# Shared_IoT_Dev.net
KiCad netlist of a schematic drawn in Altium Designer
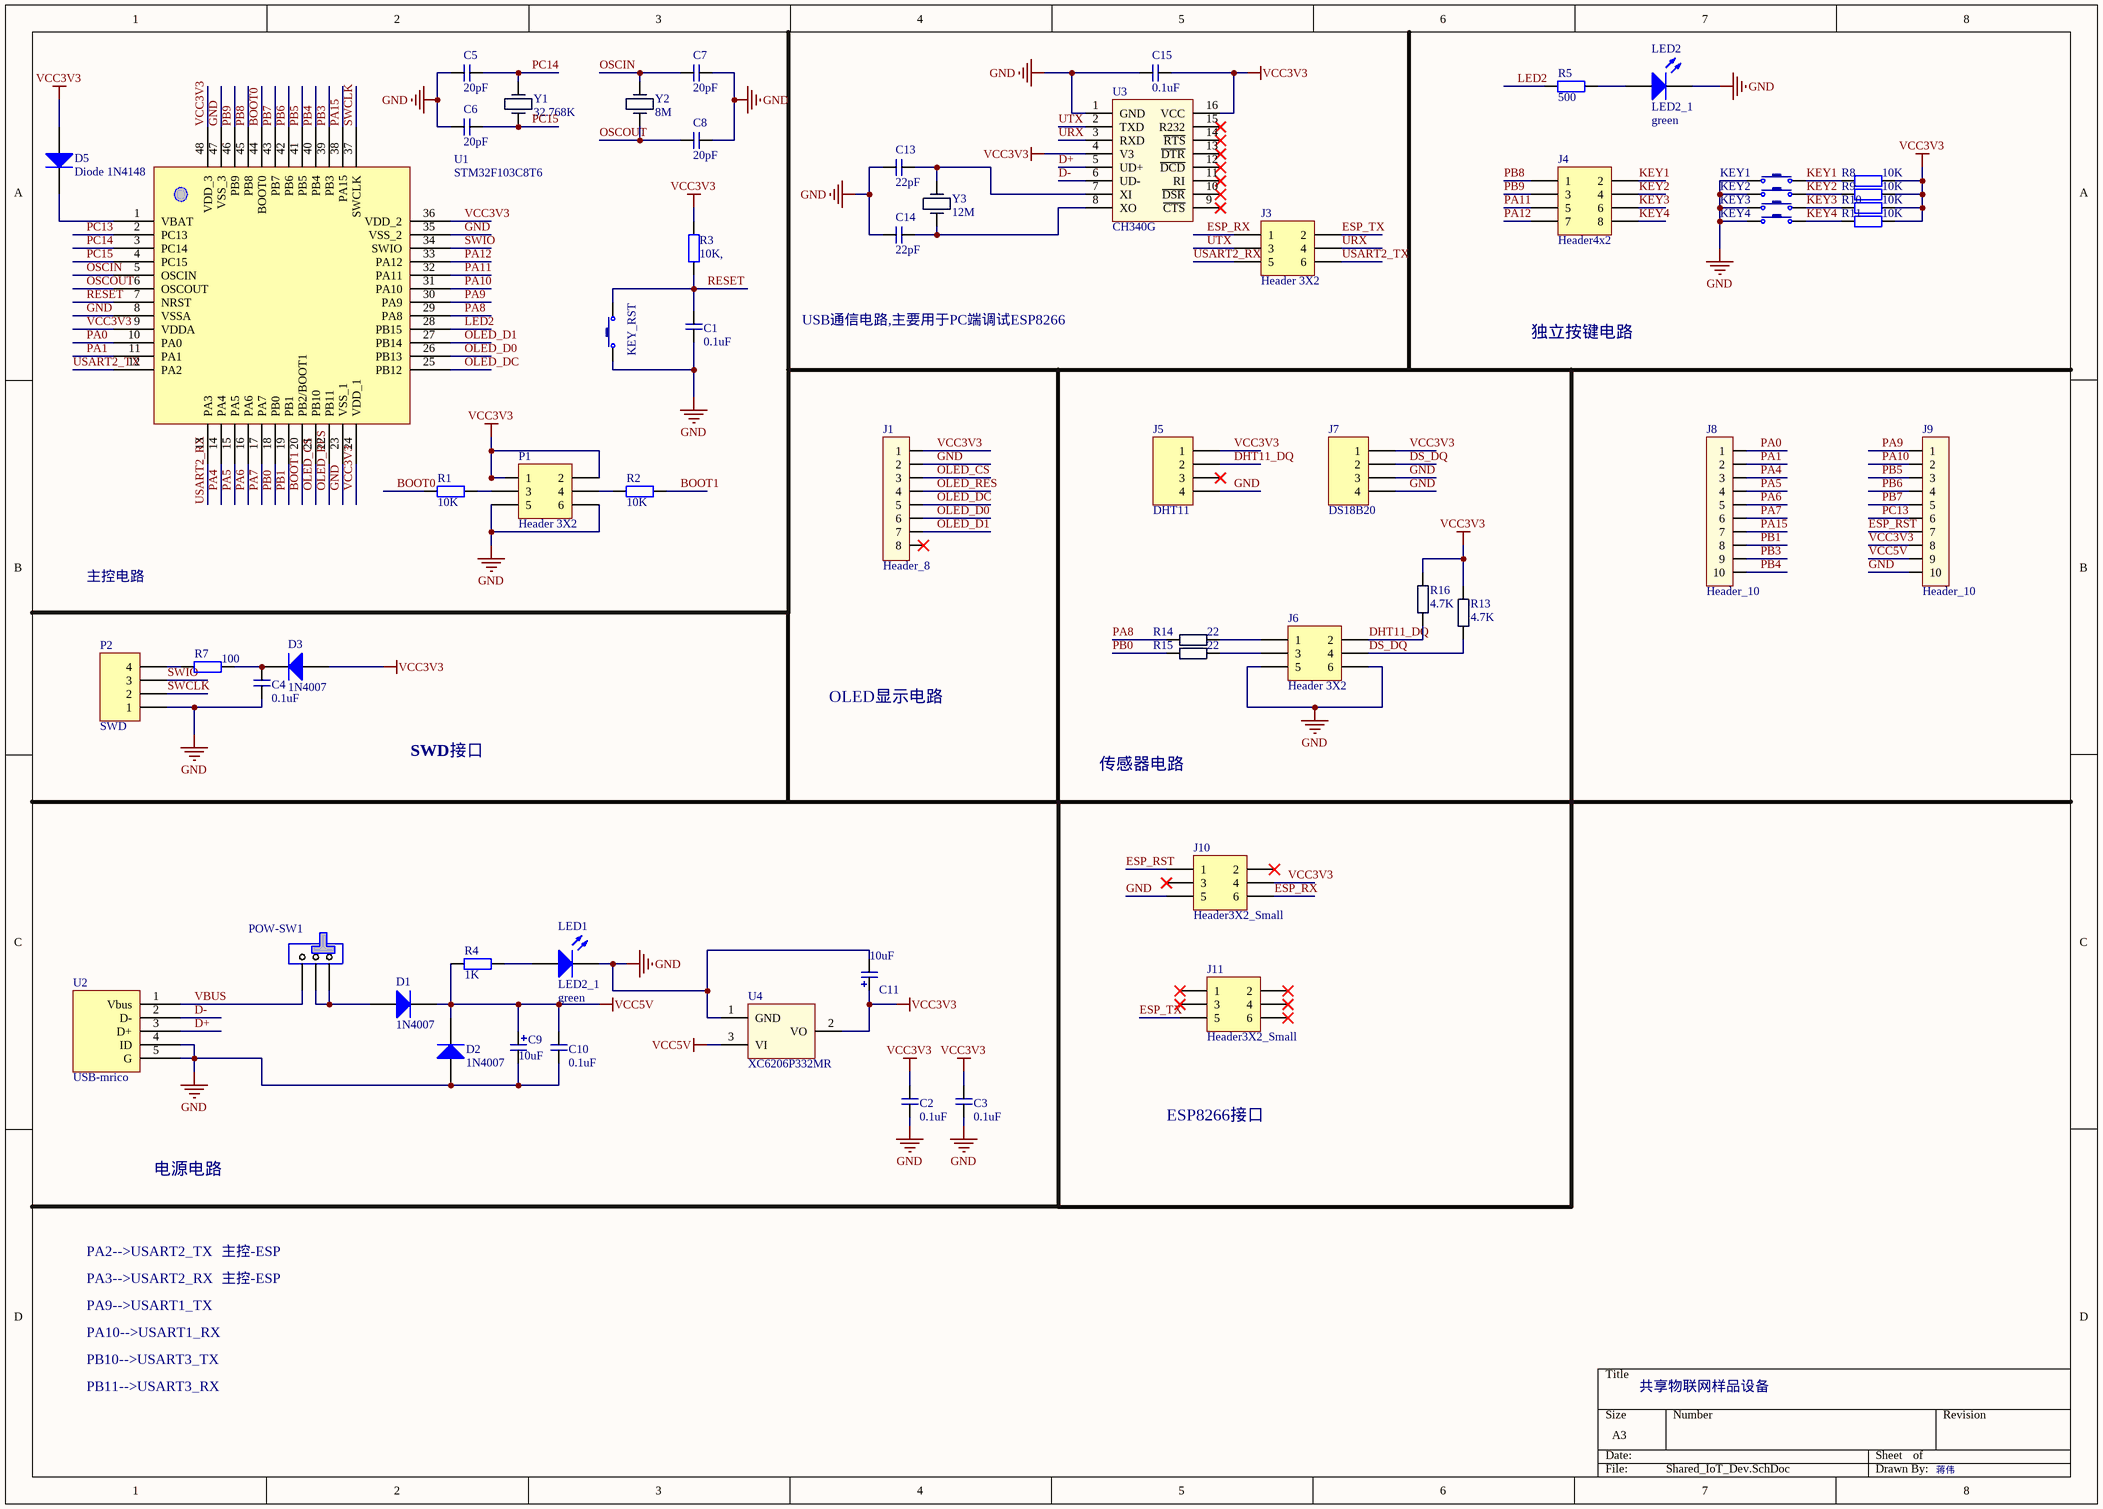
[diagram p0: Shared_IoT_Dev.SchDoc]

(export (version "E")
  (design (tool "Eeschema 10.0.6"))
  (components
    (comp (ref "C1")
      (value "0.1uF")
      (footprint "C0805")
      (description "CAP")
      (libsource (lib "Arduino") (part "CAP"))
    )
    (comp (ref "C2")
      (value "0.1uF")
      (footprint "C0805")
      (description "CAP")
      (libsource (lib "Arduino") (part "CAP"))
    )
    (comp (ref "C3")
      (value "0.1uF")
      (footprint "C0805")
      (description "CAP")
      (libsource (lib "Arduino") (part "CAP"))
    )
    (comp (ref "C4")
      (value "0.1uF")
      (footprint "C0805")
      (description "CAP")
      (libsource (lib "Arduino") (part "CAP"))
    )
    (comp (ref "C5")
      (value "20pF")
      (footprint "C0805")
      (description "CAP")
      (libsource (lib "Arduino") (part "CAP"))
    )
    (comp (ref "C6")
      (value "20pF")
      (footprint "C0805")
      (description "CAP")
      (libsource (lib "Arduino") (part "CAP"))
    )
    (comp (ref "C7")
      (value "20pF")
      (footprint "C0805")
      (description "CAP")
      (libsource (lib "Arduino") (part "CAP"))
    )
    (comp (ref "C8")
      (value "20pF")
      (footprint "C0805")
      (description "CAP")
      (libsource (lib "Arduino") (part "CAP"))
    )
    (comp (ref "C9")
      (value "10uF")
      (footprint "CAP-TH_POL")
      (description "CAP_POL")
      (libsource (lib "Arduino") (part "CAP_POL"))
    )
    (comp (ref "C10")
      (value "0.1uF")
      (footprint "C0805")
      (description "CAP")
      (libsource (lib "Arduino") (part "CAP"))
    )
    (comp (ref "C11")
      (value "10uF")
      (footprint "CAP-TH_POL")
      (description "CAP_POL")
      (libsource (lib "Arduino") (part "CAP_POL"))
    )
    (comp (ref "C13")
      (value "22pF")
      (footprint "C0805")
      (description "CAP")
      (libsource (lib "Arduino") (part "CAP"))
    )
    (comp (ref "C14")
      (value "22pF")
      (footprint "C0805")
      (description "CAP")
      (libsource (lib "Arduino") (part "CAP"))
    )
    (comp (ref "C15")
      (value "0.1uF")
      (footprint "C0805")
      (description "CAP")
      (libsource (lib "Arduino") (part "CAP"))
    )
    (comp (ref "D1") (value "1N4007") (footprint "SMA") (libsource (lib "电流测量仪仪主控板原理图7950") (part "DIODE")))
    (comp (ref "D2") (value "1N4007") (footprint "SMA") (libsource (lib "电流测量仪仪主控板原理图7950") (part "DIODE")))
    (comp (ref "D3") (value "1N4007") (footprint "SMA") (libsource (lib "电流测量仪仪主控板原理图7950") (part "DIODE")))
    (comp (ref "D5")
      (value "Diode 1N4148")
      (footprint "SMA")
      (description "High Conductance Fast Diode")
      (fields (field (name "PUBLISHER") "Altium Limited"))
      (libsource (lib "电流测量仪仪主控板原理图7950") (part "Diode 1N4148"))
    )
    (comp (ref "J1")
      (value "Header_8")
      (footprint "HDR-TH_8P-P2.54-V")
      (libsource (lib "Arduino") (part "Header_8"))
    )
    (comp (ref "J3")
      (value "Header 3X2")
      (footprint "HDR2X3")
      (description "Header, 3-Pin, Dual row")
      (fields (field (name "PUBLISHER") "Altium Limited"))
      (libsource (lib "STM32F103C8T6") (part "Header 3X2"))
    )
    (comp (ref "J4")
      (value "Header4x2")
      (footprint "HDR2X4")
      (libsource (lib "STM32F103C8T6") (part "Header4x2"))
    )
    (comp (ref "J5")
      (value "DHT11")
      (footprint "HDR1X4H")
      (description "Header, 4-Pin")
      (fields (field (name "PUBLISHER") "Altium Limited"))
      (libsource (lib "") (part "Header 4_1"))
    )
    (comp (ref "J6")
      (value "Header 3X2")
      (footprint "HDR2X3")
      (description "Header, 3-Pin, Dual row")
      (fields (field (name "PUBLISHER") "Altium Limited"))
      (libsource (lib "STM32F103C8T6") (part "Header 3X2"))
    )
    (comp (ref "J7")
      (value "DS18B20")
      (footprint "HDR1X4H")
      (description "Header, 4-Pin")
      (fields (field (name "PUBLISHER") "Altium Limited"))
      (libsource (lib "") (part "Header 4_1"))
    )
    (comp (ref "J8")
      (value "Header_10")
      (footprint "HDR-TH_10P-P2.54-V")
      (libsource (lib "") (part "Header_10_1"))
    )
    (comp (ref "J9")
      (value "Header_10")
      (footprint "HDR-TH_10P-P2.54-V")
      (libsource (lib "Arduino") (part "Header_10"))
    )
    (comp (ref "J10")
      (value "Header3X2_Small")
      (footprint "HDR3X2_Small")
      (libsource (lib "STM32F103C8T6") (part "Header3X2_Small"))
    )
    (comp (ref "J11")
      (value "Header3X2_Small")
      (footprint "HDR3X2_Small")
      (libsource (lib "STM32F103C8T6") (part "Header3X2_Small"))
    )
    (comp (ref "KEY1") (value "KEY") (footprint "KEY-TH_4P") (libsource (lib "Arduino") (part "KEY")))
    (comp (ref "KEY2") (value "KEY") (footprint "KEY-TH_4P") (libsource (lib "Arduino") (part "KEY")))
    (comp (ref "KEY3") (value "KEY") (footprint "KEY-TH_4P") (libsource (lib "Arduino") (part "KEY")))
    (comp (ref "KEY4") (value "KEY") (footprint "KEY-TH_4P") (libsource (lib "Arduino") (part "KEY")))
    (comp (ref "KEY_RST") (value "KEY") (footprint "KEY-TH_4P") (libsource (lib "Arduino") (part "KEY")))
    (comp (ref "LED1")
      (value "LED2_1")
      (footprint "0805C")
      (description "Typical RED, GREEN, YELLOW, AMBER GaAs LED")
      (fields (field (name "ALTIUM_UNNAMED_1") "green") (field (name "PUBLISHER") "Altium Limited"))
      (libsource (lib "电流测量仪仪主控板原理图7950") (part "LED2_1"))
    )
    (comp (ref "LED2")
      (value "LED2_1")
      (footprint "0805C")
      (description "Typical RED, GREEN, YELLOW, AMBER GaAs LED")
      (fields (field (name "ALTIUM_UNNAMED_1") "green") (field (name "PUBLISHER") "Altium Limited"))
      (libsource (lib "电流测量仪仪主控板原理图7950") (part "LED2_1"))
    )
    (comp (ref "P1")
      (value "Header 3X2")
      (footprint "HDR2X3")
      (description "Header, 3-Pin, Dual row")
      (fields (field (name "PUBLISHER") "Altium Limited"))
      (libsource (lib "STM32F103C8T6") (part "Header 3X2"))
    )
    (comp (ref "P2")
      (value "SWD")
      (footprint "HDR1X4H")
      (description "Header, 4-Pin")
      (fields (field (name "PUBLISHER") "Altium Limited"))
      (libsource (lib "STM32F103C8T6") (part "Header 4"))
    )
    (comp (ref "POW-SW1")
      (value "Switch")
      (footprint "SW")
      (libsource (lib "电流测量仪仪主控板原理图7950") (part "Swich_On_Off"))
    )
    (comp (ref "R1")
      (value "10K")
      (footprint "R0805")
      (description "Resistor")
      (fields (field (name "PUBLISHER") "Altium Limited"))
      (libsource (lib "STM32F103C8T6") (part "Res2"))
    )
    (comp (ref "R2")
      (value "10K")
      (footprint "R0805")
      (description "Resistor")
      (fields (field (name "PUBLISHER") "Altium Limited"))
      (libsource (lib "STM32F103C8T6") (part "Res2"))
    )
    (comp (ref "R3")
      (value "10K,")
      (footprint "R0805")
      (description "Resistor")
      (fields (field (name "PUBLISHER") "Altium Limited"))
      (libsource (lib "") (part "Res2_1"))
    )
    (comp (ref "R4")
      (value "1K")
      (footprint "0805R")
      (description "Resistor")
      (fields (field (name "Comment") "Res2") (field (name "PUBLISHER") "Altium Limited"))
      (libsource (lib "电流测量仪仪主控板原理图7950") (part "Res_3"))
    )
    (comp (ref "R5")
      (value "500")
      (footprint "0805R")
      (description "Resistor")
      (fields (field (name "Comment") "Res2") (field (name "PUBLISHER") "Altium Limited"))
      (libsource (lib "电流测量仪仪主控板原理图7950") (part "Res_3"))
    )
    (comp (ref "R7")
      (value "100")
      (footprint "0805R")
      (description "Resistor")
      (fields (field (name "PUBLISHER") "Altium Limited"))
      (libsource (lib "电流测量仪仪主控板原理图7950") (part "Res2"))
    )
    (comp (ref "R8")
      (value "10K")
      (footprint "0805R")
      (description "Resistor")
      (fields (field (name "Comment") "Res2") (field (name "PUBLISHER") "Altium Limited"))
      (libsource (lib "电流测量仪仪主控板原理图7950") (part "Res_3"))
    )
    (comp (ref "R9")
      (value "10K")
      (footprint "0805R")
      (description "Resistor")
      (fields (field (name "Comment") "Res2") (field (name "PUBLISHER") "Altium Limited"))
      (libsource (lib "电流测量仪仪主控板原理图7950") (part "Res_3"))
    )
    (comp (ref "R10")
      (value "10K")
      (footprint "0805R")
      (description "Resistor")
      (fields (field (name "Comment") "Res2") (field (name "PUBLISHER") "Altium Limited"))
      (libsource (lib "电流测量仪仪主控板原理图7950") (part "Res_3"))
    )
    (comp (ref "R11")
      (value "10K")
      (footprint "0805R")
      (description "Resistor")
      (fields (field (name "Comment") "Res2") (field (name "PUBLISHER") "Altium Limited"))
      (libsource (lib "电流测量仪仪主控板原理图7950") (part "Res_3"))
    )
    (comp (ref "R13")
      (value "4.7K")
      (footprint "R0805")
      (description "RES")
      (libsource (lib "Arduino") (part "RES"))
    )
    (comp (ref "R14")
      (value "22")
      (footprint "R0805")
      (description "RES")
      (libsource (lib "Arduino") (part "RES"))
    )
    (comp (ref "R15")
      (value "22")
      (footprint "R0805")
      (description "RES")
      (libsource (lib "Arduino") (part "RES"))
    )
    (comp (ref "R16")
      (value "4.7K")
      (footprint "R0805")
      (description "RES")
      (libsource (lib "Arduino") (part "RES"))
    )
    (comp (ref "U1")
      (value "STM32F103C8T6")
      (footprint "48P")
      (libsource (lib "STM32F103C8T6") (part "STM32F103C8T6"))
    )
    (comp (ref "U2")
      (value "USB-mrico")
      (footprint "Micro_USB")
      (libsource (lib "STM32F103C8T6") (part "usb-STM"))
    )
    (comp (ref "U3") (value "CH340G") (footprint "CH340G_SOIC") (libsource (lib "Arduino") (part "CH340G")))
    (comp (ref "U4")
      (value "XC6206P332MR")
      (footprint "XC_SOT-23-3")
      (description "XC6206P332MR Power Lower to 3.3v")
      (libsource (lib "Arduino") (part "XC6206P332MR"))
    )
    (comp (ref "Y1")
      (value "32.768K")
      (footprint "CRYSTAL")
      (description "CRYSTAL")
      (libsource (lib "Arduino") (part "CRYSTAL"))
    )
    (comp (ref "Y2")
      (value "8M")
      (footprint "CRYSTAL")
      (description "CRYSTAL")
      (libsource (lib "Arduino") (part "CRYSTAL"))
    )
    (comp (ref "Y3")
      (value "12M")
      (footprint "CRYSTAL")
      (description "CRYSTAL")
      (libsource (lib "Arduino") (part "CRYSTAL"))
    )
  )
  (nets
    (net (code "1") (name "/BOOT0") (class "Default")
      (node (ref "R1") (pin "1") (pinfunction "1_1") (pintype "passive"))
      (node (ref "U1") (pin "44") (pinfunction "BOOT0_44") (pintype "passive"))
    )
    (net (code "2") (name "/BOOT1") (class "Default")
      (node (ref "R2") (pin "2") (pinfunction "2_2") (pintype "passive"))
      (node (ref "U1") (pin "20") (pinfunction "PB2/BOOT1_20") (pintype "passive"))
    )
    (net (code "3") (name "/D+") (class "Default")
      (node (ref "U2") (pin "3") (pinfunction "D+_3") (pintype "passive"))
      (node (ref "U3") (pin "5") (pinfunction "UD+_5") (pintype "passive"))
    )
    (net (code "4") (name "/D-") (class "Default")
      (node (ref "U2") (pin "2") (pinfunction "D-_2") (pintype "passive"))
      (node (ref "U3") (pin "6") (pinfunction "UD-_6") (pintype "passive"))
    )
    (net (code "5") (name "/DHT11_DQ") (class "Default")
      (node (ref "J5") (pin "2") (pinfunction "2_2") (pintype "passive"))
      (node (ref "J6") (pin "2") (pinfunction "2_2") (pintype "passive"))
      (node (ref "R16") (pin "1") (pinfunction "1_1") (pintype "passive"))
    )
    (net (code "6") (name "/DS_DQ") (class "Default")
      (node (ref "J6") (pin "4") (pinfunction "4_4") (pintype "passive"))
      (node (ref "J7") (pin "2") (pinfunction "2_2") (pintype "passive"))
      (node (ref "R13") (pin "1") (pinfunction "1_1") (pintype "passive"))
    )
    (net (code "7") (name "/ESP_RST") (class "Default")
      (node (ref "J10") (pin "1") (pinfunction "1_1") (pintype "passive"))
      (node (ref "J9") (pin "7") (pinfunction "7_7") (pintype "passive"))
    )
    (net (code "8") (name "/ESP_RX") (class "Default")
      (node (ref "J10") (pin "6") (pinfunction "6_6") (pintype "passive"))
      (node (ref "J3") (pin "1") (pinfunction "1_1") (pintype "passive"))
    )
    (net (code "9") (name "/ESP_TX") (class "Default")
      (node (ref "J11") (pin "5") (pinfunction "5_5") (pintype "passive"))
      (node (ref "J3") (pin "2") (pinfunction "2_2") (pintype "passive"))
    )
    (net (code "10") (name "/KEY1") (class "Default")
      (node (ref "J4") (pin "2") (pinfunction "2_2") (pintype "passive"))
      (node (ref "KEY1") (pin "3") (pinfunction "3_3") (pintype "passive"))
      (node (ref "R8") (pin "1") (pinfunction "1_1") (pintype "passive"))
    )
    (net (code "11") (name "/KEY2") (class "Default")
      (node (ref "J4") (pin "4") (pinfunction "4_4") (pintype "passive"))
      (node (ref "KEY2") (pin "3") (pinfunction "3_3") (pintype "passive"))
      (node (ref "R9") (pin "1") (pinfunction "1_1") (pintype "passive"))
    )
    (net (code "12") (name "/KEY3") (class "Default")
      (node (ref "J4") (pin "6") (pinfunction "6_6") (pintype "passive"))
      (node (ref "KEY3") (pin "3") (pinfunction "3_3") (pintype "passive"))
      (node (ref "R10") (pin "1") (pinfunction "1_1") (pintype "passive"))
    )
    (net (code "13") (name "/KEY4") (class "Default")
      (node (ref "J4") (pin "8") (pinfunction "8_8") (pintype "passive"))
      (node (ref "KEY4") (pin "3") (pinfunction "3_3") (pintype "passive"))
      (node (ref "R11") (pin "1") (pinfunction "1_1") (pintype "passive"))
    )
    (net (code "14") (name "/LED2") (class "Default")
      (node (ref "R5") (pin "1") (pinfunction "1_1") (pintype "passive"))
      (node (ref "U1") (pin "28") (pinfunction "PB15_28") (pintype "passive"))
    )
    (net (code "15") (name "/OLED_CS") (class "Default")
      (node (ref "J1") (pin "3") (pinfunction "3_3") (pintype "passive"))
      (node (ref "U1") (pin "21") (pinfunction "PB10_21") (pintype "passive"))
    )
    (net (code "16") (name "/OLED_D0") (class "Default")
      (node (ref "J1") (pin "6") (pinfunction "6_6") (pintype "passive"))
      (node (ref "U1") (pin "26") (pinfunction "PB13_26") (pintype "passive"))
    )
    (net (code "17") (name "/OLED_D1") (class "Default")
      (node (ref "J1") (pin "7") (pinfunction "7_7") (pintype "passive"))
      (node (ref "U1") (pin "27") (pinfunction "PB14_27") (pintype "passive"))
    )
    (net (code "18") (name "/OLED_DC") (class "Default")
      (node (ref "J1") (pin "5") (pinfunction "5_5") (pintype "passive"))
      (node (ref "U1") (pin "25") (pinfunction "PB12_25") (pintype "passive"))
    )
    (net (code "19") (name "/OLED_RES") (class "Default")
      (node (ref "J1") (pin "4") (pinfunction "4_4") (pintype "passive"))
      (node (ref "U1") (pin "22") (pinfunction "PB11_22") (pintype "passive"))
    )
    (net (code "20") (name "/OSCIN") (class "Default")
      (node (ref "C7") (pin "1") (pinfunction "1_1") (pintype "passive"))
      (node (ref "U1") (pin "5") (pinfunction "OSCIN_5") (pintype "passive"))
      (node (ref "Y2") (pin "2") (pinfunction "2_2") (pintype "passive"))
    )
    (net (code "21") (name "/OSCOUT") (class "Default")
      (node (ref "C8") (pin "1") (pinfunction "1_1") (pintype "passive"))
      (node (ref "U1") (pin "6") (pinfunction "OSCOUT_6") (pintype "passive"))
      (node (ref "Y2") (pin "1") (pinfunction "1_1") (pintype "passive"))
    )
    (net (code "22") (name "/PA0") (class "Default")
      (node (ref "J8") (pin "1") (pinfunction "1_1") (pintype "passive"))
      (node (ref "U1") (pin "10") (pinfunction "PA0_10") (pintype "passive"))
    )
    (net (code "23") (name "/PA1") (class "Default")
      (node (ref "J8") (pin "2") (pinfunction "2_2") (pintype "passive"))
      (node (ref "U1") (pin "11") (pinfunction "PA1_11") (pintype "passive"))
    )
    (net (code "24") (name "/PA4") (class "Default")
      (node (ref "J8") (pin "3") (pinfunction "3_3") (pintype "passive"))
      (node (ref "U1") (pin "14") (pinfunction "PA4_14") (pintype "passive"))
    )
    (net (code "25") (name "/PA5") (class "Default")
      (node (ref "J8") (pin "4") (pinfunction "4_4") (pintype "passive"))
      (node (ref "U1") (pin "15") (pinfunction "PA5_15") (pintype "passive"))
    )
    (net (code "26") (name "/PA6") (class "Default")
      (node (ref "J8") (pin "5") (pinfunction "5_5") (pintype "passive"))
      (node (ref "U1") (pin "16") (pinfunction "PA6_16") (pintype "passive"))
    )
    (net (code "27") (name "/PA7") (class "Default")
      (node (ref "J8") (pin "6") (pinfunction "6_6") (pintype "passive"))
      (node (ref "U1") (pin "17") (pinfunction "PA7_17") (pintype "passive"))
    )
    (net (code "28") (name "/PA8") (class "Default")
      (node (ref "R14") (pin "2") (pinfunction "2_2") (pintype "passive"))
      (node (ref "U1") (pin "29") (pinfunction "PA8_29") (pintype "passive"))
    )
    (net (code "29") (name "/PA9") (class "Default")
      (node (ref "J9") (pin "1") (pinfunction "1_1") (pintype "passive"))
      (node (ref "U1") (pin "30") (pinfunction "PA9_30") (pintype "passive"))
    )
    (net (code "30") (name "/PA10") (class "Default")
      (node (ref "J9") (pin "2") (pinfunction "2_2") (pintype "passive"))
      (node (ref "U1") (pin "31") (pinfunction "PA10_31") (pintype "passive"))
    )
    (net (code "31") (name "/PA11") (class "Default")
      (node (ref "J4") (pin "5") (pinfunction "5_5") (pintype "passive"))
      (node (ref "U1") (pin "32") (pinfunction "PA11_32") (pintype "passive"))
    )
    (net (code "32") (name "/PA12") (class "Default")
      (node (ref "J4") (pin "7") (pinfunction "7_7") (pintype "passive"))
      (node (ref "U1") (pin "33") (pinfunction "PA12_33") (pintype "passive"))
    )
    (net (code "33") (name "/PA15") (class "Default")
      (node (ref "J8") (pin "7") (pinfunction "7_7") (pintype "passive"))
      (node (ref "U1") (pin "38") (pinfunction "PA15_38") (pintype "passive"))
    )
    (net (code "34") (name "/PB0") (class "Default")
      (node (ref "R15") (pin "2") (pinfunction "2_2") (pintype "passive"))
      (node (ref "U1") (pin "18") (pinfunction "PB0_18") (pintype "passive"))
    )
    (net (code "35") (name "/PB1") (class "Default")
      (node (ref "J8") (pin "8") (pinfunction "8_8") (pintype "passive"))
      (node (ref "U1") (pin "19") (pinfunction "PB1_19") (pintype "passive"))
    )
    (net (code "36") (name "/PB3") (class "Default")
      (node (ref "J8") (pin "9") (pinfunction "9_9") (pintype "passive"))
      (node (ref "U1") (pin "39") (pinfunction "PB3_39") (pintype "passive"))
    )
    (net (code "37") (name "/PB4") (class "Default")
      (node (ref "J8") (pin "10") (pinfunction "10_10") (pintype "passive"))
      (node (ref "U1") (pin "40") (pinfunction "PB4_40") (pintype "passive"))
    )
    (net (code "38") (name "/PB5") (class "Default")
      (node (ref "J9") (pin "3") (pinfunction "3_3") (pintype "passive"))
      (node (ref "U1") (pin "41") (pinfunction "PB5_41") (pintype "passive"))
    )
    (net (code "39") (name "/PB6") (class "Default")
      (node (ref "J9") (pin "4") (pinfunction "4_4") (pintype "passive"))
      (node (ref "U1") (pin "42") (pinfunction "PB6_42") (pintype "passive"))
    )
    (net (code "40") (name "/PB7") (class "Default")
      (node (ref "J9") (pin "5") (pinfunction "5_5") (pintype "passive"))
      (node (ref "U1") (pin "43") (pinfunction "PB7_43") (pintype "passive"))
    )
    (net (code "41") (name "/PB8") (class "Default")
      (node (ref "J4") (pin "1") (pinfunction "1_1") (pintype "passive"))
      (node (ref "U1") (pin "45") (pinfunction "PB8_45") (pintype "passive"))
    )
    (net (code "42") (name "/PB9") (class "Default")
      (node (ref "J4") (pin "3") (pinfunction "3_3") (pintype "passive"))
      (node (ref "U1") (pin "46") (pinfunction "PB9_46") (pintype "passive"))
    )
    (net (code "43") (name "/PC13") (class "Default")
      (node (ref "J9") (pin "6") (pinfunction "6_6") (pintype "passive"))
      (node (ref "U1") (pin "2") (pinfunction "PC13_2") (pintype "passive"))
    )
    (net (code "44") (name "/PC14") (class "Default")
      (node (ref "C5") (pin "2") (pinfunction "2_2") (pintype "passive"))
      (node (ref "U1") (pin "3") (pinfunction "PC14_3") (pintype "passive"))
      (node (ref "Y1") (pin "2") (pinfunction "2_2") (pintype "passive"))
    )
    (net (code "45") (name "/PC15") (class "Default")
      (node (ref "C6") (pin "2") (pinfunction "2_2") (pintype "passive"))
      (node (ref "U1") (pin "4") (pinfunction "PC15_4") (pintype "passive"))
      (node (ref "Y1") (pin "1") (pinfunction "1_1") (pintype "passive"))
    )
    (net (code "46") (name "/RESET") (class "Default")
      (node (ref "C1") (pin "1") (pinfunction "1_1") (pintype "passive"))
      (node (ref "KEY_RST") (pin "3") (pinfunction "3_3") (pintype "passive"))
      (node (ref "R3") (pin "1") (pinfunction "1_1") (pintype "passive"))
      (node (ref "U1") (pin "7") (pinfunction "NRST_7") (pintype "passive"))
    )
    (net (code "47") (name "/SWCLK") (class "Default")
      (node (ref "P2") (pin "2") (pinfunction "2_2") (pintype "passive"))
      (node (ref "U1") (pin "37") (pinfunction "SWCLK_37") (pintype "passive"))
    )
    (net (code "48") (name "/SWIO") (class "Default")
      (node (ref "P2") (pin "3") (pinfunction "3_3") (pintype "passive"))
      (node (ref "U1") (pin "34") (pinfunction "SWIO_34") (pintype "passive"))
    )
    (net (code "49") (name "/URX") (class "Default")
      (node (ref "J3") (pin "4") (pinfunction "4_4") (pintype "passive"))
      (node (ref "U3") (pin "3") (pinfunction "RXD_3") (pintype "passive"))
    )
    (net (code "50") (name "/USART2_RX") (class "Default")
      (node (ref "J3") (pin "5") (pinfunction "5_5") (pintype "passive"))
      (node (ref "U1") (pin "13") (pinfunction "PA3_13") (pintype "passive"))
    )
    (net (code "51") (name "/USART2_TX") (class "Default")
      (node (ref "J3") (pin "6") (pinfunction "6_6") (pintype "passive"))
      (node (ref "U1") (pin "12") (pinfunction "PA2_12") (pintype "passive"))
    )
    (net (code "52") (name "/UTX") (class "Default")
      (node (ref "J3") (pin "3") (pinfunction "3_3") (pintype "passive"))
      (node (ref "U3") (pin "2") (pinfunction "TXD_2") (pintype "passive"))
    )
    (net (code "53") (name "/VBUS") (class "Default")
      (node (ref "POW-SW1") (pin "1") (pinfunction "1_1") (pintype "passive"))
      (node (ref "U2") (pin "1") (pinfunction "Vbus_1") (pintype "passive"))
    )
    (net (code "54") (name "GND") (class "Default")
      (node (ref "C1") (pin "2") (pinfunction "2_2") (pintype "passive"))
      (node (ref "C10") (pin "1") (pinfunction "1_1") (pintype "passive"))
      (node (ref "C11") (pin "2") (pinfunction "2_2") (pintype "passive"))
      (node (ref "C13") (pin "2") (pinfunction "2_2") (pintype "passive"))
      (node (ref "C14") (pin "2") (pinfunction "2_2") (pintype "passive"))
      (node (ref "C15") (pin "2") (pinfunction "2_2") (pintype "passive"))
      (node (ref "C2") (pin "2") (pinfunction "2_2") (pintype "passive"))
      (node (ref "C3") (pin "2") (pinfunction "2_2") (pintype "passive"))
      (node (ref "C4") (pin "2") (pinfunction "2_2") (pintype "passive"))
      (node (ref "C5") (pin "1") (pinfunction "1_1") (pintype "passive"))
      (node (ref "C6") (pin "1") (pinfunction "1_1") (pintype "passive"))
      (node (ref "C7") (pin "2") (pinfunction "2_2") (pintype "passive"))
      (node (ref "C8") (pin "2") (pinfunction "2_2") (pintype "passive"))
      (node (ref "C9") (pin "2") (pinfunction "2_2") (pintype "passive"))
      (node (ref "D2") (pin "1") (pinfunction "A_1") (pintype "passive"))
      (node (ref "J1") (pin "2") (pinfunction "2_2") (pintype "passive"))
      (node (ref "J10") (pin "5") (pinfunction "5_5") (pintype "passive"))
      (node (ref "J5") (pin "4") (pinfunction "4_4") (pintype "passive"))
      (node (ref "J6") (pin "5") (pinfunction "5_5") (pintype "passive"))
      (node (ref "J6") (pin "6") (pinfunction "6_6") (pintype "passive"))
      (node (ref "J7") (pin "3") (pinfunction "3_3") (pintype "passive"))
      (node (ref "J7") (pin "4") (pinfunction "4_4") (pintype "passive"))
      (node (ref "J9") (pin "10") (pinfunction "10_10") (pintype "passive"))
      (node (ref "KEY1") (pin "1") (pinfunction "1_1") (pintype "passive"))
      (node (ref "KEY2") (pin "1") (pinfunction "1_1") (pintype "passive"))
      (node (ref "KEY3") (pin "1") (pinfunction "1_1") (pintype "passive"))
      (node (ref "KEY4") (pin "1") (pinfunction "1_1") (pintype "passive"))
      (node (ref "KEY_RST") (pin "1") (pinfunction "1_1") (pintype "passive"))
      (node (ref "LED1") (pin "2") (pinfunction "K_2") (pintype "passive"))
      (node (ref "LED2") (pin "2") (pinfunction "K_2") (pintype "passive"))
      (node (ref "P1") (pin "5") (pinfunction "5_5") (pintype "passive"))
      (node (ref "P1") (pin "6") (pinfunction "6_6") (pintype "passive"))
      (node (ref "P2") (pin "1") (pinfunction "1_1") (pintype "passive"))
      (node (ref "U1") (pin "23") (pinfunction "VSS_1_23") (pintype "passive"))
      (node (ref "U1") (pin "35") (pinfunction "VSS_2_35") (pintype "passive"))
      (node (ref "U1") (pin "47") (pinfunction "VSS_3_47") (pintype "passive"))
      (node (ref "U1") (pin "8") (pinfunction "VSSA_8") (pintype "passive"))
      (node (ref "U2") (pin "4") (pinfunction "ID_4") (pintype "passive"))
      (node (ref "U2") (pin "5") (pinfunction "G_5") (pintype "passive"))
      (node (ref "U3") (pin "1") (pinfunction "GND_1") (pintype "passive"))
      (node (ref "U4") (pin "1") (pinfunction "GND_1") (pintype "passive"))
    )
    (net (code "55") (name "Net-(D1-A)") (class "Default")
      (node (ref "D1") (pin "1") (pinfunction "A_1") (pintype "passive"))
      (node (ref "POW-SW1") (pin "2") (pinfunction "2_2") (pintype "passive"))
      (node (ref "POW-SW1") (pin "3") (pinfunction "3_3") (pintype "passive"))
    )
    (net (code "56") (name "Net-(D3-K)") (class "Default")
      (node (ref "C4") (pin "1") (pinfunction "1_1") (pintype "passive"))
      (node (ref "D3") (pin "2") (pinfunction "K_2") (pintype "passive"))
      (node (ref "R7") (pin "2") (pinfunction "2_2") (pintype "passive"))
    )
    (net (code "57") (name "Net-(D5-K)") (class "Default")
      (node (ref "D5") (pin "2") (pinfunction "K_2") (pintype "passive"))
      (node (ref "U1") (pin "1") (pinfunction "VBAT_1") (pintype "passive"))
    )
    (net (code "58") (name "Net-(J6-Pad1)") (class "Default")
      (node (ref "J6") (pin "1") (pinfunction "1_1") (pintype "passive"))
      (node (ref "R14") (pin "1") (pinfunction "1_1") (pintype "passive"))
    )
    (net (code "59") (name "Net-(J6-Pad3)") (class "Default")
      (node (ref "J6") (pin "3") (pinfunction "3_3") (pintype "passive"))
      (node (ref "R15") (pin "1") (pinfunction "1_1") (pintype "passive"))
    )
    (net (code "60") (name "Net-(LED1-A)") (class "Default")
      (node (ref "LED1") (pin "1") (pinfunction "A_1") (pintype "passive"))
      (node (ref "R4") (pin "2") (pinfunction "2_2") (pintype "passive"))
    )
    (net (code "61") (name "Net-(LED2-A)") (class "Default")
      (node (ref "LED2") (pin "1") (pinfunction "A_1") (pintype "passive"))
      (node (ref "R5") (pin "2") (pinfunction "2_2") (pintype "passive"))
    )
    (net (code "62") (name "Net-(P1-Pad3)") (class "Default")
      (node (ref "P1") (pin "3") (pinfunction "3_3") (pintype "passive"))
      (node (ref "R1") (pin "2") (pinfunction "2_2") (pintype "passive"))
    )
    (net (code "63") (name "Net-(P1-Pad4)") (class "Default")
      (node (ref "P1") (pin "4") (pinfunction "4_4") (pintype "passive"))
      (node (ref "R2") (pin "1") (pinfunction "1_1") (pintype "passive"))
    )
    (net (code "64") (name "Net-(P2-Pad4)") (class "Default")
      (node (ref "P2") (pin "4") (pinfunction "4_4") (pintype "passive"))
      (node (ref "R7") (pin "1") (pinfunction "1_1") (pintype "passive"))
    )
    (net (code "65") (name "Net-(U3-XI)") (class "Default")
      (node (ref "C13") (pin "1") (pinfunction "1_1") (pintype "passive"))
      (node (ref "U3") (pin "7") (pinfunction "XI_7") (pintype "passive"))
      (node (ref "Y3") (pin "2") (pinfunction "2_2") (pintype "passive"))
    )
    (net (code "66") (name "Net-(U3-XO)") (class "Default")
      (node (ref "C14") (pin "1") (pinfunction "1_1") (pintype "passive"))
      (node (ref "U3") (pin "8") (pinfunction "XO_8") (pintype "passive"))
      (node (ref "Y3") (pin "1") (pinfunction "1_1") (pintype "passive"))
    )
    (net (code "67") (name "VCC3V3") (class "Default")
      (node (ref "C11") (pin "1") (pinfunction "1_1") (pintype "passive"))
      (node (ref "C15") (pin "1") (pinfunction "1_1") (pintype "passive"))
      (node (ref "C2") (pin "1") (pinfunction "1_1") (pintype "passive"))
      (node (ref "C3") (pin "1") (pinfunction "1_1") (pintype "passive"))
      (node (ref "D3") (pin "1") (pinfunction "A_1") (pintype "passive"))
      (node (ref "D5") (pin "1") (pinfunction "A_1") (pintype "passive"))
      (node (ref "J1") (pin "1") (pinfunction "1_1") (pintype "passive"))
      (node (ref "J10") (pin "4") (pinfunction "4_4") (pintype "passive"))
      (node (ref "J5") (pin "1") (pinfunction "1_1") (pintype "passive"))
      (node (ref "J7") (pin "1") (pinfunction "1_1") (pintype "passive"))
      (node (ref "J9") (pin "8") (pinfunction "8_8") (pintype "passive"))
      (node (ref "P1") (pin "1") (pinfunction "1_1") (pintype "passive"))
      (node (ref "P1") (pin "2") (pinfunction "2_2") (pintype "passive"))
      (node (ref "R10") (pin "2") (pinfunction "2_2") (pintype "passive"))
      (node (ref "R11") (pin "2") (pinfunction "2_2") (pintype "passive"))
      (node (ref "R13") (pin "2") (pinfunction "2_2") (pintype "passive"))
      (node (ref "R16") (pin "2") (pinfunction "2_2") (pintype "passive"))
      (node (ref "R3") (pin "2") (pinfunction "2_2") (pintype "passive"))
      (node (ref "R8") (pin "2") (pinfunction "2_2") (pintype "passive"))
      (node (ref "R9") (pin "2") (pinfunction "2_2") (pintype "passive"))
      (node (ref "U1") (pin "24") (pinfunction "VDD_1_24") (pintype "passive"))
      (node (ref "U1") (pin "36") (pinfunction "VDD_2_36") (pintype "passive"))
      (node (ref "U1") (pin "48") (pinfunction "VDD_3_48") (pintype "passive"))
      (node (ref "U1") (pin "9") (pinfunction "VDDA_9") (pintype "passive"))
      (node (ref "U3") (pin "16") (pinfunction "VCC_16") (pintype "passive"))
      (node (ref "U3") (pin "4") (pinfunction "V3_4") (pintype "passive"))
      (node (ref "U4") (pin "2") (pinfunction "VO_2") (pintype "passive"))
    )
    (net (code "68") (name "VCC5V") (class "Default")
      (node (ref "C10") (pin "2") (pinfunction "2_2") (pintype "passive"))
      (node (ref "C9") (pin "1") (pinfunction "1_1") (pintype "passive"))
      (node (ref "D1") (pin "2") (pinfunction "K_2") (pintype "passive"))
      (node (ref "D2") (pin "2") (pinfunction "K_2") (pintype "passive"))
      (node (ref "J9") (pin "9") (pinfunction "9_9") (pintype "passive"))
      (node (ref "R4") (pin "1") (pinfunction "1_1") (pintype "passive"))
      (node (ref "U4") (pin "3") (pinfunction "VI_3") (pintype "passive"))
    )
    (net (code "69") (name "unconnected-(J1-Pad8)") (class "Default")
      (node (ref "J1") (pin "8") (pinfunction "8_8") (pintype "passive+no_connect"))
    )
    (net (code "70") (name "unconnected-(J5-Pad3)") (class "Default")
      (node (ref "J5") (pin "3") (pinfunction "3_3") (pintype "passive+no_connect"))
    )
    (net (code "71") (name "unconnected-(J10-Pad2)") (class "Default")
      (node (ref "J10") (pin "2") (pinfunction "2_2") (pintype "passive+no_connect"))
    )
    (net (code "72") (name "unconnected-(J10-Pad3)") (class "Default")
      (node (ref "J10") (pin "3") (pinfunction "3_3") (pintype "passive+no_connect"))
    )
    (net (code "73") (name "unconnected-(J11-Pad1)") (class "Default")
      (node (ref "J11") (pin "1") (pinfunction "1_1") (pintype "passive+no_connect"))
    )
    (net (code "74") (name "unconnected-(J11-Pad2)") (class "Default")
      (node (ref "J11") (pin "2") (pinfunction "2_2") (pintype "passive+no_connect"))
    )
    (net (code "75") (name "unconnected-(J11-Pad3)") (class "Default")
      (node (ref "J11") (pin "3") (pinfunction "3_3") (pintype "passive+no_connect"))
    )
    (net (code "76") (name "unconnected-(J11-Pad4)") (class "Default")
      (node (ref "J11") (pin "4") (pinfunction "4_4") (pintype "passive+no_connect"))
    )
    (net (code "77") (name "unconnected-(J11-Pad6)") (class "Default")
      (node (ref "J11") (pin "6") (pinfunction "6_6") (pintype "passive+no_connect"))
    )
    (net (code "78") (name "unconnected-(KEY1-Pad2)") (class "Default")
      (node (ref "KEY1") (pin "2") (pinfunction "2_2") (pintype "passive"))
    )
    (net (code "79") (name "unconnected-(KEY1-Pad4)") (class "Default")
      (node (ref "KEY1") (pin "4") (pinfunction "4_4") (pintype "passive"))
    )
    (net (code "80") (name "unconnected-(KEY2-Pad2)") (class "Default")
      (node (ref "KEY2") (pin "2") (pinfunction "2_2") (pintype "passive"))
    )
    (net (code "81") (name "unconnected-(KEY2-Pad4)") (class "Default")
      (node (ref "KEY2") (pin "4") (pinfunction "4_4") (pintype "passive"))
    )
    (net (code "82") (name "unconnected-(KEY3-Pad2)") (class "Default")
      (node (ref "KEY3") (pin "2") (pinfunction "2_2") (pintype "passive"))
    )
    (net (code "83") (name "unconnected-(KEY3-Pad4)") (class "Default")
      (node (ref "KEY3") (pin "4") (pinfunction "4_4") (pintype "passive"))
    )
    (net (code "84") (name "unconnected-(KEY4-Pad2)") (class "Default")
      (node (ref "KEY4") (pin "2") (pinfunction "2_2") (pintype "passive"))
    )
    (net (code "85") (name "unconnected-(KEY4-Pad4)") (class "Default")
      (node (ref "KEY4") (pin "4") (pinfunction "4_4") (pintype "passive"))
    )
    (net (code "86") (name "unconnected-(KEY_RST-Pad2)") (class "Default")
      (node (ref "KEY_RST") (pin "2") (pinfunction "2_2") (pintype "passive"))
    )
    (net (code "87") (name "unconnected-(KEY_RST-Pad4)") (class "Default")
      (node (ref "KEY_RST") (pin "4") (pinfunction "4_4") (pintype "passive"))
    )
    (net (code "88") (name "unconnected-(U3-R232-Pad15)") (class "Default")
      (node (ref "U3") (pin "15") (pinfunction "R232_15") (pintype "passive+no_connect"))
    )
    (net (code "89") (name "unconnected-(U3-RI-Pad11)") (class "Default")
      (node (ref "U3") (pin "11") (pinfunction "RI_11") (pintype "passive+no_connect"))
    )
    (net (code "90") (name "unconnected-(U3-~{CTS}-Pad9)") (class "Default")
      (node (ref "U3") (pin "9") (pinfunction "~{CTS}_9") (pintype "passive+no_connect"))
    )
    (net (code "91") (name "unconnected-(U3-~{DCD}-Pad12)") (class "Default")
      (node (ref "U3") (pin "12") (pinfunction "~{DCD}_12") (pintype "passive+no_connect"))
    )
    (net (code "92") (name "unconnected-(U3-~{DSR}-Pad10)") (class "Default")
      (node (ref "U3") (pin "10") (pinfunction "~{DSR}_10") (pintype "passive+no_connect"))
    )
    (net (code "93") (name "unconnected-(U3-~{DTR}-Pad13)") (class "Default")
      (node (ref "U3") (pin "13") (pinfunction "~{DTR}_13") (pintype "passive+no_connect"))
    )
    (net (code "94") (name "unconnected-(U3-~{RTS}-Pad14)") (class "Default")
      (node (ref "U3") (pin "14") (pinfunction "~{RTS}_14") (pintype "passive+no_connect"))
    )
  )
)
